# v1.net
KiCad netlist of a schematic drawn in EAGLE
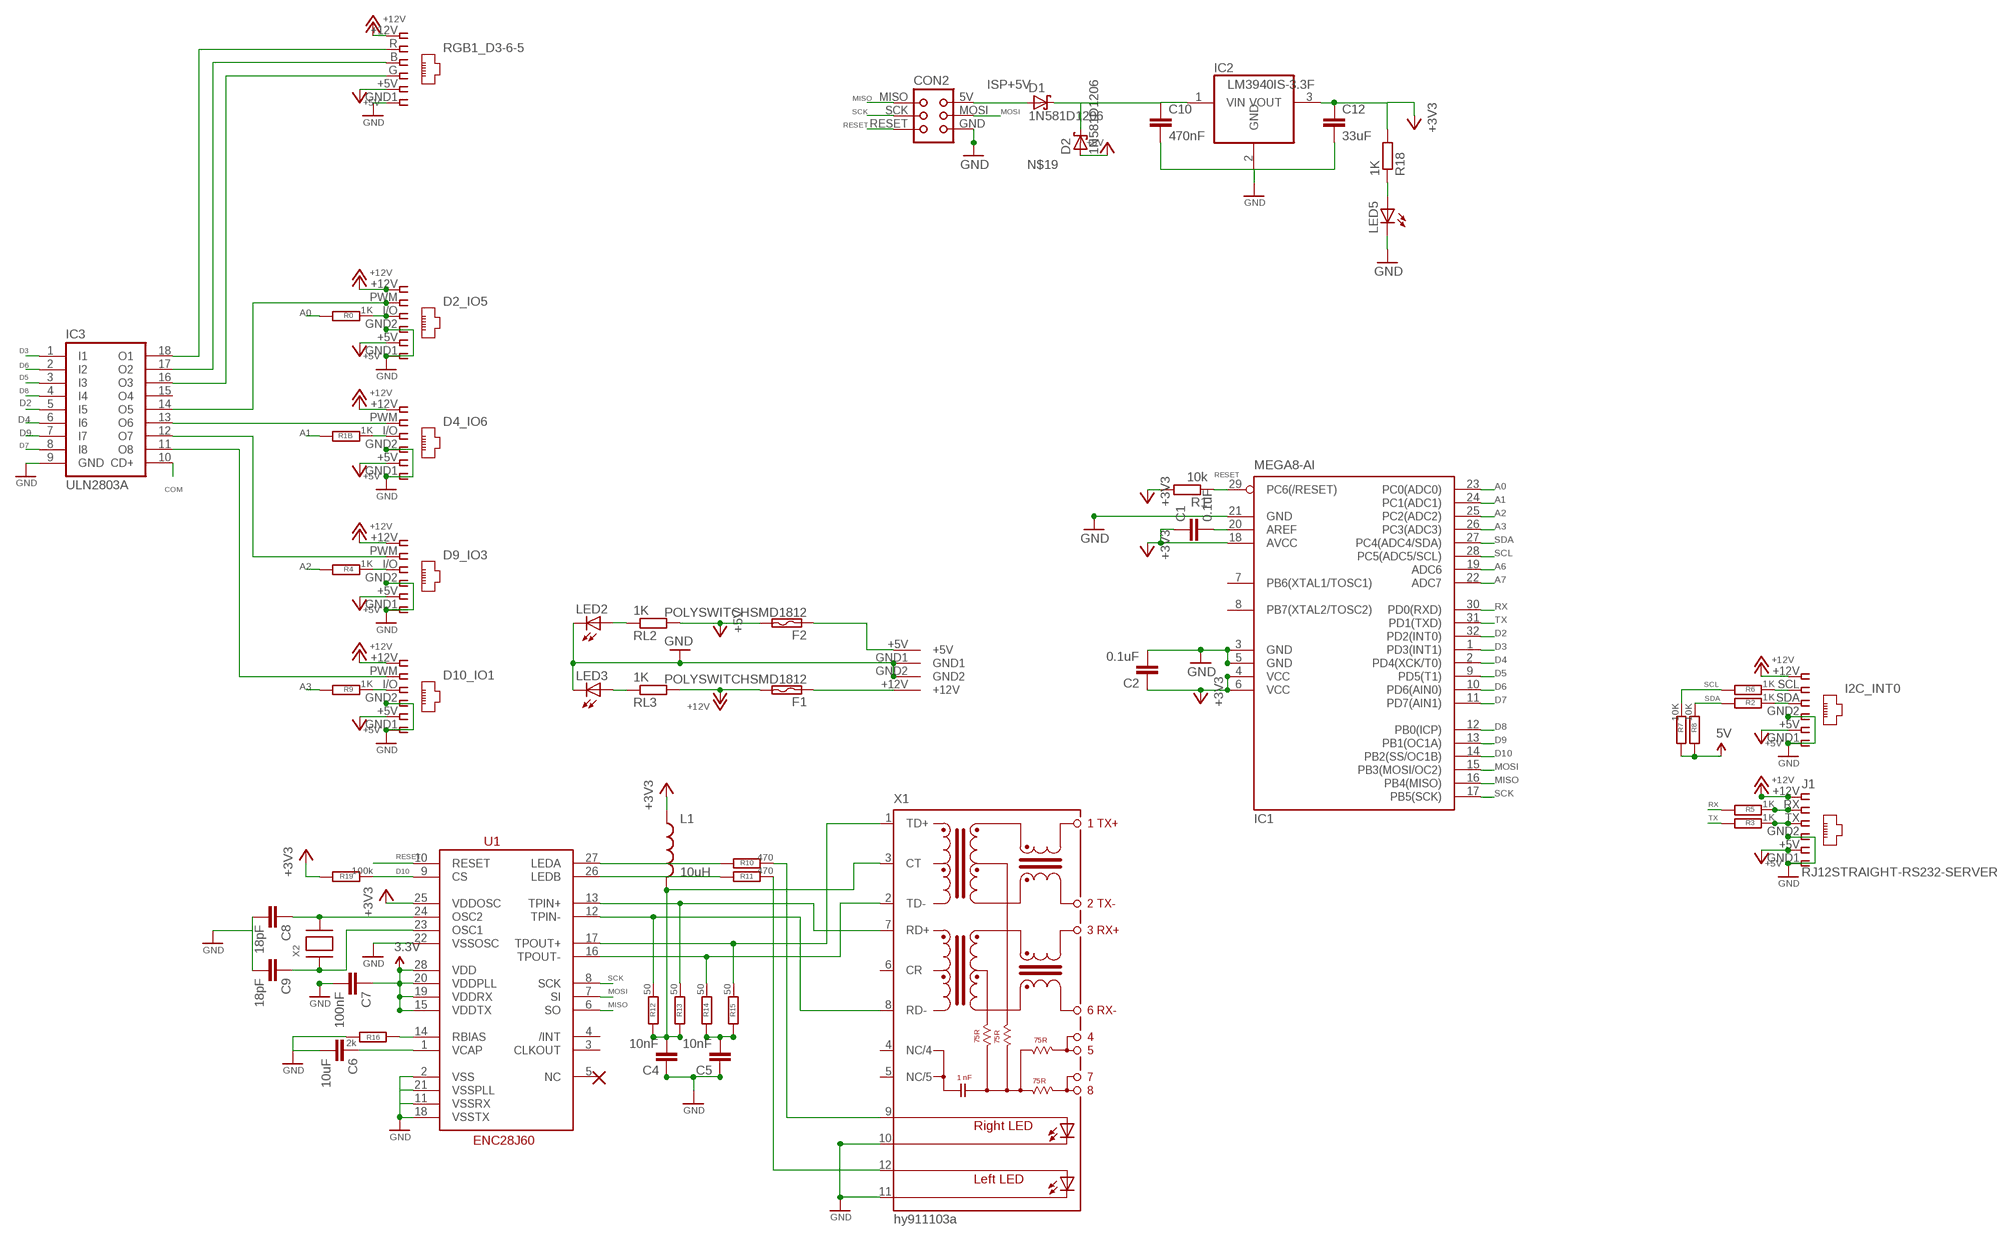
[diagram p0: schematic, sheet 1]

(export (version "E")
  (design (tool "Eeschema 10.0.6"))
  (components
    (comp (ref "C1")
      (value "0.1uF")
      (footprint "eagle-import:C1206")
      (libsource (lib "eagle-import") (part "resistor_C-EUC1206"))
    )
    (comp (ref "C2")
      (value "0.1uF")
      (footprint "eagle-import:C1206")
      (libsource (lib "eagle-import") (part "resistor_C-EUC1206"))
    )
    (comp (ref "C4")
      (value "10nF")
      (footprint "eagle-import:C1206")
      (libsource (lib "eagle-import") (part "resistor_C-EUC1206"))
    )
    (comp (ref "C5")
      (value "10nF")
      (footprint "eagle-import:C1206")
      (libsource (lib "eagle-import") (part "resistor_C-EUC1206"))
    )
    (comp (ref "C6")
      (value "10uF")
      (footprint "eagle-import:C1206")
      (libsource (lib "eagle-import") (part "resistor_C-EUC1206"))
    )
    (comp (ref "C7")
      (value "100nF")
      (footprint "eagle-import:C1206")
      (libsource (lib "eagle-import") (part "resistor_C-EUC1206"))
    )
    (comp (ref "C8")
      (value "18pF")
      (footprint "eagle-import:C1206")
      (libsource (lib "eagle-import") (part "resistor_C-EUC1206"))
    )
    (comp (ref "C9")
      (value "18pF")
      (footprint "eagle-import:C1206")
      (libsource (lib "eagle-import") (part "resistor_C-EUC1206"))
    )
    (comp (ref "C10")
      (value "470nF")
      (footprint "eagle-import:C1206")
      (libsource (lib "eagle-import") (part "C-EUC1206"))
    )
    (comp (ref "C12")
      (value "33uF")
      (footprint "eagle-import:1210")
      (libsource (lib "eagle-import") (part "CAP1210"))
    )
    (comp (ref "CON2")
      (value "TINYISPTAG")
      (footprint "eagle-import:TC2030-MCP")
      (libsource (lib "eagle-import") (part "TINYISPTAG"))
    )
    (comp (ref "D1")
      (value "1N581D1206")
      (footprint "eagle-import:LED-1206")
      (libsource (lib "eagle-import") (part "1N581D1206"))
    )
    (comp (ref "D2")
      (value "1N581D1206")
      (footprint "eagle-import:LED-1206")
      (libsource (lib "eagle-import") (part "1N581D1206"))
    )
    (comp (ref "D2_IO5")
      (value "IO5")
      (footprint "eagle-import:RJ12-STRAIGHT")
      (libsource (lib "eagle-import") (part "RJ12STRAIGHT"))
    )
    (comp (ref "D4_IO6")
      (value "IO6")
      (footprint "eagle-import:RJ12-STRAIGHT")
      (libsource (lib "eagle-import") (part "RJ12STRAIGHT"))
    )
    (comp (ref "D9_IO3")
      (value "IO3")
      (footprint "eagle-import:RJ12-STRAIGHT")
      (libsource (lib "eagle-import") (part "RJ12STRAIGHT"))
    )
    (comp (ref "D10_IO1")
      (value "IO1")
      (footprint "eagle-import:RJ12-STRAIGHT")
      (libsource (lib "eagle-import") (part "RJ12STRAIGHT"))
    )
    (comp (ref "F1")
      (value "POLYSWITCHSMD1812")
      (footprint "eagle-import:C1812")
      (libsource (lib "eagle-import") (part "POLYSWITCHSMD1812"))
    )
    (comp (ref "F2")
      (value "POLYSWITCHSMD1812")
      (footprint "eagle-import:C1812")
      (libsource (lib "eagle-import") (part "POLYSWITCHSMD1812"))
    )
    (comp (ref "I2C_INT0")
      (value "I2C")
      (footprint "eagle-import:RJ12-STRAIGHT-I2C")
      (libsource (lib "eagle-import") (part "RJ12STRAIGHT-I2C"))
    )
    (comp (ref "IC1")
      (value "MEGA8-AI")
      (footprint "eagle-import:TQFP32-08")
      (fields (field (name "MPN") "ATMEGA8-16AU"))
      (libsource (lib "eagle-import") (part "MEGA8-AI"))
    )
    (comp (ref "IC2")
      (value "LM3940IS-3.3F")
      (footprint "eagle-import:DD-3")
      (fields (field (name "MF") "TEXAS INSTRUMENTS") (field (name "MPN") "REG1117FAKTTT"))
      (libsource (lib "eagle-import") (part "LM3940IS-3.3F"))
    )
    (comp (ref "IC3")
      (value "ULN2803A")
      (footprint "eagle-import:SO18W")
      (libsource (lib "eagle-import") (part "ULN2803A"))
    )
    (comp (ref "J1")
      (value "RJ12STRAIGHT-RS232-SERVER")
      (footprint "eagle-import:RJ12-STRAIGHT-RS232")
      (libsource (lib "eagle-import") (part "RJ12STRAIGHT-RS232-SERVER"))
    )
    (comp (ref "L1")
      (value "10uH")
      (footprint "eagle-import:INDUCTOR-1206")
      (libsource (lib "eagle-import") (part "INDUCTORH1206"))
    )
    (comp (ref "LED2")
      (value "LED3MM")
      (footprint "eagle-import:LED3MM")
      (libsource (lib "eagle-import") (part "LED3MM"))
    )
    (comp (ref "LED3")
      (value "LED3MM")
      (footprint "eagle-import:LED3MM")
      (libsource (lib "eagle-import") (part "LED3MM"))
    )
    (comp (ref "LED5")
      (value "LED3MM")
      (footprint "eagle-import:LED3MM")
      (libsource (lib "eagle-import") (part "LED3MM"))
    )
    (comp (ref "R0")
      (value "1K")
      (footprint "eagle-import:M1206")
      (libsource (lib "eagle-import") (part "R-EU_M1206"))
    )
    (comp (ref "R1")
      (value "10k")
      (footprint "eagle-import:M1206")
      (libsource (lib "eagle-import") (part "R-EU_M1206"))
    )
    (comp (ref "R1B")
      (value "1K")
      (footprint "eagle-import:M1206")
      (libsource (lib "eagle-import") (part "R-EU_M1206"))
    )
    (comp (ref "R2")
      (value "1K")
      (footprint "eagle-import:M1206")
      (libsource (lib "eagle-import") (part "R-EU_M1206"))
    )
    (comp (ref "R3")
      (value "1K")
      (footprint "eagle-import:M1206")
      (libsource (lib "eagle-import") (part "R-EU_M1206"))
    )
    (comp (ref "R4")
      (value "1K")
      (footprint "eagle-import:M1206")
      (libsource (lib "eagle-import") (part "R-EU_M1206"))
    )
    (comp (ref "R5")
      (value "1K")
      (footprint "eagle-import:M1206")
      (libsource (lib "eagle-import") (part "R-EU_M1206"))
    )
    (comp (ref "R6")
      (value "1K")
      (footprint "eagle-import:M1206")
      (libsource (lib "eagle-import") (part "R-EU_M1206"))
    )
    (comp (ref "R7")
      (value "10K")
      (footprint "eagle-import:M1206")
      (libsource (lib "eagle-import") (part "R-EU_M1206"))
    )
    (comp (ref "R8")
      (value "10K")
      (footprint "eagle-import:M1206")
      (libsource (lib "eagle-import") (part "R-EU_M1206"))
    )
    (comp (ref "R9")
      (value "1K")
      (footprint "eagle-import:M1206")
      (libsource (lib "eagle-import") (part "R-EU_M1206"))
    )
    (comp (ref "R10")
      (value "470")
      (footprint "eagle-import:M1206")
      (libsource (lib "eagle-import") (part "R-EU_M1206"))
    )
    (comp (ref "R11")
      (value "470")
      (footprint "eagle-import:M1206")
      (libsource (lib "eagle-import") (part "R-EU_M1206"))
    )
    (comp (ref "R12")
      (value "50")
      (footprint "eagle-import:M1206")
      (libsource (lib "eagle-import") (part "R-EU_M1206"))
    )
    (comp (ref "R13")
      (value "50")
      (footprint "eagle-import:M1206")
      (libsource (lib "eagle-import") (part "R-EU_M1206"))
    )
    (comp (ref "R14")
      (value "50")
      (footprint "eagle-import:M1206")
      (libsource (lib "eagle-import") (part "R-EU_M1206"))
    )
    (comp (ref "R15")
      (value "50")
      (footprint "eagle-import:M1206")
      (libsource (lib "eagle-import") (part "R-EU_M1206"))
    )
    (comp (ref "R16")
      (value "2k")
      (footprint "eagle-import:M1206")
      (libsource (lib "eagle-import") (part "R-EU_M1206"))
    )
    (comp (ref "R18")
      (value "1K")
      (footprint "eagle-import:M1206")
      (libsource (lib "eagle-import") (part "R-EU_M1206"))
    )
    (comp (ref "R19")
      (value "100k")
      (footprint "eagle-import:M1206")
      (libsource (lib "eagle-import") (part "R-EU_M1206"))
    )
    (comp (ref "RGB1_D3-6-5")
      (value "RGB1")
      (footprint "eagle-import:RJ12-STRAIGHT-RGB")
      (libsource (lib "eagle-import") (part "RJ12STRAIGHT-RGB"))
    )
    (comp (ref "RL2")
      (value "1K")
      (footprint "eagle-import:M1206")
      (libsource (lib "eagle-import") (part "R-EU_M1206"))
    )
    (comp (ref "RL3")
      (value "1K")
      (footprint "eagle-import:M1206")
      (libsource (lib "eagle-import") (part "R-EU_M1206"))
    )
    (comp (ref "U$2")
      (value "KPJX-4S-S")
      (footprint "eagle-import:KPJX-4S-S")
      (libsource (lib "eagle-import") (part "KPJX-4S-S"))
    )
    (comp (ref "U1")
      (value "ENC28J60SO")
      (footprint "eagle-import:SO28W")
      (libsource (lib "eagle-import") (part "ENC28J60SO"))
    )
    (comp (ref "X1")
      (value "hy911103a")
      (footprint "eagle-import:J1")
      (libsource (lib "eagle-import") (part "J1011F01P"))
    )
    (comp (ref "X2")
      (value "XTALNX5032")
      (footprint "eagle-import:NX5032")
      (libsource (lib "eagle-import") (part "XTALNX5032"))
    )
  )
  (nets
    (net (code "1") (name "+3V3") (class "Default")
      (node (ref "C1") (pin "1") (pinfunction "1_1") (pintype "passive"))
      (node (ref "C12") (pin "1") (pinfunction "1_1") (pintype "passive"))
      (node (ref "C2") (pin "1") (pinfunction "1_1") (pintype "passive"))
      (node (ref "IC1") (pin "18") (pinfunction "AVCC_18") (pintype "power_in"))
      (node (ref "IC1") (pin "4") (pinfunction "VCC_4") (pintype "power_in"))
      (node (ref "IC1") (pin "6") (pinfunction "VCC_6") (pintype "power_in"))
      (node (ref "IC2") (pin "3") (pinfunction "VOUT_3") (pintype "output"))
      (node (ref "L1") (pin "P$1") (pinfunction "1_P$1") (pintype "passive"))
      (node (ref "R1") (pin "2") (pinfunction "2_2") (pintype "passive"))
      (node (ref "R18") (pin "2") (pinfunction "2_2") (pintype "passive"))
      (node (ref "R19") (pin "2") (pinfunction "2_2") (pintype "passive"))
      (node (ref "U1") (pin "25") (pinfunction "VDDOSC_25") (pintype "bidirectional"))
    )
    (net (code "2") (name "+5V") (class "Default")
      (node (ref "D10_IO1") (pin "+5V") (pinfunction "5_+5V") (pintype "power_in"))
      (node (ref "D2") (pin "A") (pinfunction "A_A") (pintype "passive"))
      (node (ref "D2_IO5") (pin "+5V") (pinfunction "5_+5V") (pintype "power_in"))
      (node (ref "D4_IO6") (pin "+5V") (pinfunction "5_+5V") (pintype "power_in"))
      (node (ref "D9_IO3") (pin "+5V") (pinfunction "5_+5V") (pintype "power_in"))
      (node (ref "F2") (pin "2") (pinfunction "2_2") (pintype "passive"))
      (node (ref "I2C_INT0") (pin "+5V") (pinfunction "5_+5V") (pintype "power_in"))
      (node (ref "J1") (pin "+5V") (pinfunction "5_+5V") (pintype "power_in"))
      (node (ref "RGB1_D3-6-5") (pin "+5V") (pinfunction "5_+5V") (pintype "power_in"))
      (node (ref "RL2") (pin "2") (pinfunction "2_2") (pintype "passive"))
    )
    (net (code "3") (name "+12V") (class "Default")
      (node (ref "D10_IO1") (pin "+12V") (pinfunction "1_+12V") (pintype "power_in"))
      (node (ref "D2_IO5") (pin "+12V") (pinfunction "1_+12V") (pintype "power_in"))
      (node (ref "D4_IO6") (pin "+12V") (pinfunction "1_+12V") (pintype "power_in"))
      (node (ref "D9_IO3") (pin "+12V") (pinfunction "1_+12V") (pintype "power_in"))
      (node (ref "F1") (pin "2") (pinfunction "2_2") (pintype "passive"))
      (node (ref "I2C_INT0") (pin "+12V") (pinfunction "1_+12V") (pintype "power_in"))
      (node (ref "J1") (pin "+12V") (pinfunction "1_+12V") (pintype "power_in"))
      (node (ref "RGB1_D3-6-5") (pin "+12V") (pinfunction "1_+12V") (pintype "power_in"))
      (node (ref "RL3") (pin "2") (pinfunction "2_2") (pintype "passive"))
    )
    (net (code "4") (name "/A0") (class "Default")
      (node (ref "IC1") (pin "23") (pinfunction "PC0(ADC0)_23") (pintype "bidirectional"))
      (node (ref "R0") (pin "2") (pinfunction "2_2") (pintype "passive"))
    )
    (net (code "5") (name "/A1") (class "Default")
      (node (ref "IC1") (pin "24") (pinfunction "PC1(ADC1)_24") (pintype "bidirectional"))
      (node (ref "R1B") (pin "2") (pinfunction "2_2") (pintype "passive"))
    )
    (net (code "6") (name "/A2") (class "Default")
      (node (ref "IC1") (pin "25") (pinfunction "PC2(ADC2)_25") (pintype "bidirectional"))
      (node (ref "R4") (pin "2") (pinfunction "2_2") (pintype "passive"))
    )
    (net (code "7") (name "/A3") (class "Default")
      (node (ref "IC1") (pin "26") (pinfunction "PC3(ADC3)_26") (pintype "bidirectional"))
      (node (ref "R9") (pin "2") (pinfunction "2_2") (pintype "passive"))
    )
    (net (code "8") (name "/A6") (class "Default")
      (node (ref "IC1") (pin "19") (pinfunction "ADC6_19") (pintype "bidirectional"))
    )
    (net (code "9") (name "/A7") (class "Default")
      (node (ref "IC1") (pin "22") (pinfunction "ADC7_22") (pintype "bidirectional"))
    )
    (net (code "10") (name "/COM") (class "Default")
      (node (ref "IC3") (pin "10") (pinfunction "CD+_10") (pintype "passive"))
    )
    (net (code "11") (name "/D2") (class "Default")
      (node (ref "IC1") (pin "32") (pinfunction "PD2(INT0)_32") (pintype "bidirectional"))
      (node (ref "IC3") (pin "5") (pinfunction "I5_5") (pintype "input"))
    )
    (net (code "12") (name "/D3") (class "Default")
      (node (ref "IC1") (pin "1") (pinfunction "PD3(INT1)_1") (pintype "bidirectional"))
      (node (ref "IC3") (pin "1") (pinfunction "I1_1") (pintype "input"))
    )
    (net (code "13") (name "/D4") (class "Default")
      (node (ref "IC1") (pin "2") (pinfunction "PD4(XCK/T0)_2") (pintype "bidirectional"))
      (node (ref "IC3") (pin "6") (pinfunction "I6_6") (pintype "input"))
    )
    (net (code "14") (name "/D5") (class "Default")
      (node (ref "IC1") (pin "9") (pinfunction "PD5(T1)_9") (pintype "bidirectional"))
      (node (ref "IC3") (pin "3") (pinfunction "I3_3") (pintype "input"))
    )
    (net (code "15") (name "/D6") (class "Default")
      (node (ref "IC1") (pin "10") (pinfunction "PD6(AIN0)_10") (pintype "bidirectional"))
      (node (ref "IC3") (pin "2") (pinfunction "I2_2") (pintype "input"))
    )
    (net (code "16") (name "/D7") (class "Default")
      (node (ref "IC1") (pin "11") (pinfunction "PD7(AIN1)_11") (pintype "bidirectional"))
      (node (ref "IC3") (pin "8") (pinfunction "I8_8") (pintype "input"))
    )
    (net (code "17") (name "/D8") (class "Default")
      (node (ref "IC1") (pin "12") (pinfunction "PB0(ICP)_12") (pintype "bidirectional"))
      (node (ref "IC3") (pin "4") (pinfunction "I4_4") (pintype "input"))
    )
    (net (code "18") (name "/D9") (class "Default")
      (node (ref "IC1") (pin "13") (pinfunction "PB1(OC1A)_13") (pintype "bidirectional"))
      (node (ref "IC3") (pin "7") (pinfunction "I7_7") (pintype "input"))
    )
    (net (code "19") (name "/D10") (class "Default")
      (node (ref "IC1") (pin "14") (pinfunction "PB2(SS/OC1B)_14") (pintype "bidirectional"))
      (node (ref "R19") (pin "1") (pinfunction "1_1") (pintype "passive"))
      (node (ref "U1") (pin "9") (pinfunction "CS_9") (pintype "bidirectional"))
    )
    (net (code "20") (name "/ISP+5V") (class "Default")
      (node (ref "CON2") (pin "5V") (pinfunction "VCC_5V") (pintype "passive"))
      (node (ref "D1") (pin "A") (pinfunction "A_A") (pintype "passive"))
    )
    (net (code "21") (name "/MISO") (class "Default")
      (node (ref "CON2") (pin "MISO") (pinfunction "MISO_MISO") (pintype "passive"))
      (node (ref "IC1") (pin "16") (pinfunction "PB4(MISO)_16") (pintype "bidirectional"))
      (node (ref "U1") (pin "6") (pinfunction "SO_6") (pintype "bidirectional"))
    )
    (net (code "22") (name "/MOSI") (class "Default")
      (node (ref "CON2") (pin "MOSI") (pinfunction "MOSI_MOSI") (pintype "passive"))
      (node (ref "IC1") (pin "15") (pinfunction "PB3(MOSI/OC2)_15") (pintype "bidirectional"))
      (node (ref "U1") (pin "7") (pinfunction "SI_7") (pintype "bidirectional"))
    )
    (net (code "23") (name "/N$19") (class "Default")
      (node (ref "C10") (pin "1") (pinfunction "1_1") (pintype "passive"))
      (node (ref "D1") (pin "C") (pinfunction "C_C") (pintype "passive"))
      (node (ref "D2") (pin "C") (pinfunction "C_C") (pintype "passive"))
      (node (ref "IC2") (pin "1") (pinfunction "VIN_1") (pintype "input"))
    )
    (net (code "24") (name "/RESET") (class "Default")
      (node (ref "CON2") (pin "RESET") (pinfunction "RESET_RESET") (pintype "passive"))
      (node (ref "IC1") (pin "29") (pinfunction "PC6(/RESET)_29") (pintype "bidirectional"))
      (node (ref "R1") (pin "1") (pinfunction "1_1") (pintype "passive"))
      (node (ref "U1") (pin "10") (pinfunction "RESET_10") (pintype "bidirectional"))
    )
    (net (code "25") (name "/RX") (class "Default")
      (node (ref "IC1") (pin "30") (pinfunction "PD0(RXD)_30") (pintype "bidirectional"))
      (node (ref "R5") (pin "2") (pinfunction "2_2") (pintype "passive"))
    )
    (net (code "26") (name "/SCK") (class "Default")
      (node (ref "CON2") (pin "SCK") (pinfunction "SCK_SCK") (pintype "passive"))
      (node (ref "IC1") (pin "17") (pinfunction "PB5(SCK)_17") (pintype "bidirectional"))
      (node (ref "U1") (pin "8") (pinfunction "SCK_8") (pintype "bidirectional"))
    )
    (net (code "27") (name "/SCL") (class "Default")
      (node (ref "IC1") (pin "28") (pinfunction "PC5(ADC5/SCL)_28") (pintype "bidirectional"))
      (node (ref "R6") (pin "2") (pinfunction "2_2") (pintype "passive"))
      (node (ref "R7") (pin "1") (pinfunction "1_1") (pintype "passive"))
    )
    (net (code "28") (name "/SDA") (class "Default")
      (node (ref "IC1") (pin "27") (pinfunction "PC4(ADC4/SDA)_27") (pintype "bidirectional"))
      (node (ref "R2") (pin "2") (pinfunction "2_2") (pintype "passive"))
      (node (ref "R8") (pin "1") (pinfunction "1_1") (pintype "passive"))
    )
    (net (code "29") (name "/TX") (class "Default")
      (node (ref "IC1") (pin "31") (pinfunction "PD1(TXD)_31") (pintype "bidirectional"))
      (node (ref "R3") (pin "2") (pinfunction "2_2") (pintype "passive"))
    )
    (net (code "30") (name "3.3V") (class "Default")
      (node (ref "C7") (pin "1") (pinfunction "1_1") (pintype "passive"))
      (node (ref "U1") (pin "15") (pinfunction "VDDTX_15") (pintype "bidirectional"))
      (node (ref "U1") (pin "19") (pinfunction "VDDRX_19") (pintype "bidirectional"))
      (node (ref "U1") (pin "20") (pinfunction "VDDPLL_20") (pintype "bidirectional"))
      (node (ref "U1") (pin "28") (pinfunction "VDD_28") (pintype "bidirectional"))
    )
    (net (code "31") (name "5V") (class "Default")
      (node (ref "R7") (pin "2") (pinfunction "2_2") (pintype "passive"))
      (node (ref "R8") (pin "2") (pinfunction "2_2") (pintype "passive"))
    )
    (net (code "32") (name "GND") (class "Default")
      (node (ref "C10") (pin "2") (pinfunction "2_2") (pintype "passive"))
      (node (ref "C12") (pin "2") (pinfunction "2_2") (pintype "passive"))
      (node (ref "C2") (pin "2") (pinfunction "2_2") (pintype "passive"))
      (node (ref "C4") (pin "1") (pinfunction "1_1") (pintype "passive"))
      (node (ref "C5") (pin "1") (pinfunction "1_1") (pintype "passive"))
      (node (ref "C6") (pin "2") (pinfunction "2_2") (pintype "passive"))
      (node (ref "C7") (pin "2") (pinfunction "2_2") (pintype "passive"))
      (node (ref "C8") (pin "2") (pinfunction "2_2") (pintype "passive"))
      (node (ref "C9") (pin "2") (pinfunction "2_2") (pintype "passive"))
      (node (ref "CON2") (pin "GND") (pinfunction "GND_GND") (pintype "passive"))
      (node (ref "D10_IO1") (pin "GND1") (pinfunction "6_GND1") (pintype "power_in"))
      (node (ref "D10_IO1") (pin "GND2") (pinfunction "4_GND2") (pintype "power_in"))
      (node (ref "D2_IO5") (pin "GND1") (pinfunction "6_GND1") (pintype "power_in"))
      (node (ref "D2_IO5") (pin "GND2") (pinfunction "4_GND2") (pintype "power_in"))
      (node (ref "D4_IO6") (pin "GND1") (pinfunction "6_GND1") (pintype "power_in"))
      (node (ref "D4_IO6") (pin "GND2") (pinfunction "4_GND2") (pintype "power_in"))
      (node (ref "D9_IO3") (pin "GND1") (pinfunction "6_GND1") (pintype "power_in"))
      (node (ref "D9_IO3") (pin "GND2") (pinfunction "4_GND2") (pintype "power_in"))
      (node (ref "I2C_INT0") (pin "GND1") (pinfunction "6_GND1") (pintype "power_in"))
      (node (ref "I2C_INT0") (pin "GND2") (pinfunction "4_GND2") (pintype "power_in"))
      (node (ref "IC1") (pin "21") (pinfunction "GND_21") (pintype "power_in"))
      (node (ref "IC1") (pin "3") (pinfunction "GND_3") (pintype "power_in"))
      (node (ref "IC1") (pin "5") (pinfunction "GND_5") (pintype "power_in"))
      (node (ref "IC2") (pin "2") (pinfunction "GND_2") (pintype "power_in"))
      (node (ref "IC3") (pin "9") (pinfunction "GND_9") (pintype "power_in"))
      (node (ref "J1") (pin "GND1") (pinfunction "6_GND1") (pintype "power_in"))
      (node (ref "J1") (pin "GND2") (pinfunction "4_GND2") (pintype "power_in"))
      (node (ref "LED2") (pin "K") (pinfunction "C_K") (pintype "passive"))
      (node (ref "LED3") (pin "K") (pinfunction "C_K") (pintype "passive"))
      (node (ref "LED5") (pin "K") (pinfunction "C_K") (pintype "passive"))
      (node (ref "R16") (pin "1") (pinfunction "1_1") (pintype "passive"))
      (node (ref "RGB1_D3-6-5") (pin "GND1") (pinfunction "6_GND1") (pintype "power_in"))
      (node (ref "U$2") (pin "GND1") (pinfunction "GND1_GND1") (pintype "input"))
      (node (ref "U$2") (pin "GND2") (pinfunction "GND2_GND2") (pintype "input"))
      (node (ref "U1") (pin "11") (pinfunction "VSSRX_11") (pintype "bidirectional"))
      (node (ref "U1") (pin "18") (pinfunction "VSSTX_18") (pintype "bidirectional"))
      (node (ref "U1") (pin "2") (pinfunction "VSS_2") (pintype "bidirectional"))
      (node (ref "U1") (pin "21") (pinfunction "VSSPLL_21") (pintype "bidirectional"))
      (node (ref "U1") (pin "22") (pinfunction "VSSOSC_22") (pintype "bidirectional"))
      (node (ref "X1") (pin "10") (pinfunction "C-R_10") (pintype "passive"))
      (node (ref "X1") (pin "11") (pinfunction "C-L_11") (pintype "passive"))
    )
    (net (code "33") (name "Net-(C5-Pad2)") (class "Default")
      (node (ref "C5") (pin "2") (pinfunction "2_2") (pintype "passive"))
      (node (ref "R14") (pin "2") (pinfunction "2_2") (pintype "passive"))
      (node (ref "R15") (pin "2") (pinfunction "2_2") (pintype "passive"))
    )
    (net (code "34") (name "Net-(D2_IO5-2)") (class "Default")
      (node (ref "D2_IO5") (pin "PWM") (pinfunction "2_PWM") (pintype "bidirectional"))
      (node (ref "IC3") (pin "14") (pinfunction "O5_14") (pintype "open_collector"))
    )
    (net (code "35") (name "Net-(D2_IO5-3)") (class "Default")
      (node (ref "D2_IO5") (pin "I/O") (pinfunction "3_I/O") (pintype "bidirectional"))
      (node (ref "R0") (pin "1") (pinfunction "1_1") (pintype "passive"))
    )
    (net (code "36") (name "Net-(D4_IO6-2)") (class "Default")
      (node (ref "D4_IO6") (pin "PWM") (pinfunction "2_PWM") (pintype "bidirectional"))
      (node (ref "IC3") (pin "13") (pinfunction "O6_13") (pintype "open_collector"))
    )
    (net (code "37") (name "Net-(D4_IO6-3)") (class "Default")
      (node (ref "D4_IO6") (pin "I/O") (pinfunction "3_I/O") (pintype "bidirectional"))
      (node (ref "R1B") (pin "1") (pinfunction "1_1") (pintype "passive"))
    )
    (net (code "38") (name "Net-(D9_IO3-2)") (class "Default")
      (node (ref "D9_IO3") (pin "PWM") (pinfunction "2_PWM") (pintype "bidirectional"))
      (node (ref "IC3") (pin "12") (pinfunction "O7_12") (pintype "open_collector"))
    )
    (net (code "39") (name "Net-(D9_IO3-3)") (class "Default")
      (node (ref "D9_IO3") (pin "I/O") (pinfunction "3_I/O") (pintype "bidirectional"))
      (node (ref "R4") (pin "1") (pinfunction "1_1") (pintype "passive"))
    )
    (net (code "40") (name "Net-(D10_IO1-2)") (class "Default")
      (node (ref "D10_IO1") (pin "PWM") (pinfunction "2_PWM") (pintype "bidirectional"))
      (node (ref "IC3") (pin "11") (pinfunction "O8_11") (pintype "open_collector"))
    )
    (net (code "41") (name "Net-(D10_IO1-3)") (class "Default")
      (node (ref "D10_IO1") (pin "I/O") (pinfunction "3_I/O") (pintype "bidirectional"))
      (node (ref "R9") (pin "1") (pinfunction "1_1") (pintype "passive"))
    )
    (net (code "42") (name "Net-(F1-Pad1)") (class "Default")
      (node (ref "F1") (pin "1") (pinfunction "1_1") (pintype "passive"))
      (node (ref "U$2") (pin "+12V") (pinfunction "+12V_+12V") (pintype "power_in"))
    )
    (net (code "43") (name "Net-(F2-Pad1)") (class "Default")
      (node (ref "F2") (pin "1") (pinfunction "1_1") (pintype "passive"))
      (node (ref "U$2") (pin "+5V") (pinfunction "+5V_+5V") (pintype "power_in"))
    )
    (net (code "44") (name "Net-(I2C_INT0-2)") (class "Default")
      (node (ref "I2C_INT0") (pin "SCL") (pinfunction "2_SCL") (pintype "bidirectional"))
      (node (ref "R6") (pin "1") (pinfunction "1_1") (pintype "passive"))
    )
    (net (code "45") (name "Net-(I2C_INT0-3)") (class "Default")
      (node (ref "I2C_INT0") (pin "SDA") (pinfunction "3_SDA") (pintype "bidirectional"))
      (node (ref "R2") (pin "1") (pinfunction "1_1") (pintype "passive"))
    )
    (net (code "46") (name "Net-(IC1-AREF)") (class "Default")
      (node (ref "C1") (pin "2") (pinfunction "2_2") (pintype "passive"))
      (node (ref "IC1") (pin "20") (pinfunction "AREF_20") (pintype "passive"))
    )
    (net (code "47") (name "Net-(IC3-O1)") (class "Default")
      (node (ref "IC3") (pin "18") (pinfunction "O1_18") (pintype "open_collector"))
      (node (ref "RGB1_D3-6-5") (pin "R") (pinfunction "2_R") (pintype "bidirectional"))
    )
    (net (code "48") (name "Net-(IC3-O2)") (class "Default")
      (node (ref "IC3") (pin "17") (pinfunction "O2_17") (pintype "open_collector"))
      (node (ref "RGB1_D3-6-5") (pin "B") (pinfunction "3_B") (pintype "bidirectional"))
    )
    (net (code "49") (name "Net-(IC3-O3)") (class "Default")
      (node (ref "IC3") (pin "16") (pinfunction "O3_16") (pintype "open_collector"))
      (node (ref "RGB1_D3-6-5") (pin "G") (pinfunction "4_G") (pintype "power_in"))
    )
    (net (code "50") (name "Net-(J1-2)") (class "Default")
      (node (ref "J1") (pin "RX") (pinfunction "2_RX") (pintype "bidirectional"))
      (node (ref "R5") (pin "1") (pinfunction "1_1") (pintype "passive"))
    )
    (net (code "51") (name "Net-(J1-3)") (class "Default")
      (node (ref "J1") (pin "TX") (pinfunction "3_TX") (pintype "bidirectional"))
      (node (ref "R3") (pin "1") (pinfunction "1_1") (pintype "passive"))
    )
    (net (code "52") (name "Net-(L1-2)") (class "Default")
      (node (ref "C4") (pin "2") (pinfunction "2_2") (pintype "passive"))
      (node (ref "L1") (pin "P$2") (pinfunction "2_P$2") (pintype "passive"))
      (node (ref "R12") (pin "2") (pinfunction "2_2") (pintype "passive"))
      (node (ref "R13") (pin "2") (pinfunction "2_2") (pintype "passive"))
      (node (ref "X1") (pin "3") (pinfunction "CT_3") (pintype "input"))
    )
    (net (code "53") (name "Net-(LED2-PadA)") (class "Default")
      (node (ref "LED2") (pin "A") (pinfunction "A_A") (pintype "passive"))
      (node (ref "RL2") (pin "1") (pinfunction "1_1") (pintype "passive"))
    )
    (net (code "54") (name "Net-(LED3-PadA)") (class "Default")
      (node (ref "LED3") (pin "A") (pinfunction "A_A") (pintype "passive"))
      (node (ref "RL3") (pin "1") (pinfunction "1_1") (pintype "passive"))
    )
    (net (code "55") (name "Net-(LED5-PadA)") (class "Default")
      (node (ref "LED5") (pin "A") (pinfunction "A_A") (pintype "passive"))
      (node (ref "R18") (pin "1") (pinfunction "1_1") (pintype "passive"))
    )
    (net (code "56") (name "Net-(U1-LEDA)") (class "Default")
      (node (ref "R10") (pin "2") (pinfunction "2_2") (pintype "passive"))
      (node (ref "U1") (pin "27") (pinfunction "LEDA_27") (pintype "bidirectional"))
    )
    (net (code "57") (name "Net-(U1-LEDB)") (class "Default")
      (node (ref "R11") (pin "2") (pinfunction "2_2") (pintype "passive"))
      (node (ref "U1") (pin "26") (pinfunction "LEDB_26") (pintype "bidirectional"))
    )
    (net (code "58") (name "Net-(U1-OSC1)") (class "Default")
      (node (ref "C9") (pin "1") (pinfunction "1_1") (pintype "passive"))
      (node (ref "U1") (pin "23") (pinfunction "OSC1_23") (pintype "bidirectional"))
      (node (ref "X2") (pin "P$1") (pinfunction "P$1_P$1") (pintype "bidirectional"))
    )
    (net (code "59") (name "Net-(U1-OSC2)") (class "Default")
      (node (ref "C8") (pin "1") (pinfunction "1_1") (pintype "passive"))
      (node (ref "U1") (pin "24") (pinfunction "OSC2_24") (pintype "bidirectional"))
      (node (ref "X2") (pin "P$2") (pinfunction "P$2_P$2") (pintype "bidirectional"))
    )
    (net (code "60") (name "Net-(U1-RBIAS)") (class "Default")
      (node (ref "R16") (pin "2") (pinfunction "2_2") (pintype "passive"))
      (node (ref "U1") (pin "14") (pinfunction "RBIAS_14") (pintype "bidirectional"))
    )
    (net (code "61") (name "Net-(U1-TPIN+)") (class "Default")
      (node (ref "R13") (pin "1") (pinfunction "1_1") (pintype "passive"))
      (node (ref "U1") (pin "13") (pinfunction "TPIN+_13") (pintype "bidirectional"))
      (node (ref "X1") (pin "7") (pinfunction "RD+_7") (pintype "input"))
    )
    (net (code "62") (name "Net-(U1-TPIN-)") (class "Default")
      (node (ref "R12") (pin "1") (pinfunction "1_1") (pintype "passive"))
      (node (ref "U1") (pin "12") (pinfunction "TPIN-_12") (pintype "bidirectional"))
      (node (ref "X1") (pin "8") (pinfunction "RD-_8") (pintype "input"))
    )
    (net (code "63") (name "Net-(U1-TPOUT+)") (class "Default")
      (node (ref "R15") (pin "1") (pinfunction "1_1") (pintype "passive"))
      (node (ref "U1") (pin "17") (pinfunction "TPOUT+_17") (pintype "bidirectional"))
      (node (ref "X1") (pin "1") (pinfunction "TD+_1") (pintype "input"))
    )
    (net (code "64") (name "Net-(U1-TPOUT-)") (class "Default")
      (node (ref "R14") (pin "1") (pinfunction "1_1") (pintype "passive"))
      (node (ref "U1") (pin "16") (pinfunction "TPOUT-_16") (pintype "bidirectional"))
      (node (ref "X1") (pin "2") (pinfunction "TD-_2") (pintype "input"))
    )
    (net (code "65") (name "Net-(U1-VCAP)") (class "Default")
      (node (ref "C6") (pin "1") (pinfunction "1_1") (pintype "passive"))
      (node (ref "U1") (pin "1") (pinfunction "VCAP_1") (pintype "bidirectional"))
    )
    (net (code "66") (name "Net-(X1-A-R)") (class "Default")
      (node (ref "R10") (pin "1") (pinfunction "1_1") (pintype "passive"))
      (node (ref "X1") (pin "9") (pinfunction "A-R_9") (pintype "passive"))
    )
    (net (code "67") (name "Net-(X1-AL)") (class "Default")
      (node (ref "R11") (pin "1") (pinfunction "1_1") (pintype "passive"))
      (node (ref "X1") (pin "12") (pinfunction "AL_12") (pintype "passive"))
    )
    (net (code "68") (name "unconnected-(IC1-PB6(XTAL1{slash}TOSC1)-Pad7)") (class "Default")
      (node (ref "IC1") (pin "7") (pinfunction "PB6(XTAL1/TOSC1)_7") (pintype "bidirectional"))
    )
    (net (code "69") (name "unconnected-(IC1-PB7(XTAL2{slash}TOSC2)-Pad8)") (class "Default")
      (node (ref "IC1") (pin "8") (pinfunction "PB7(XTAL2/TOSC2)_8") (pintype "bidirectional"))
    )
    (net (code "70") (name "unconnected-(IC3-O4-Pad15)") (class "Default")
      (node (ref "IC3") (pin "15") (pinfunction "O4_15") (pintype "open_collector"))
    )
    (net (code "71") (name "unconnected-(U1-CLKOUT-Pad3)") (class "Default")
      (node (ref "U1") (pin "3") (pinfunction "CLKOUT_3") (pintype "bidirectional"))
    )
    (net (code "72") (name "unconnected-(U1-NC-Pad5)") (class "Default")
      (node (ref "U1") (pin "5") (pinfunction "NC_5") (pintype "bidirectional"))
    )
    (net (code "73") (name "unconnected-(U1-{slash}INT-Pad4)") (class "Default")
      (node (ref "U1") (pin "4") (pinfunction "/INT_4") (pintype "bidirectional"))
    )
    (net (code "74") (name "unconnected-(X1-CR-Pad6)") (class "Default")
      (node (ref "X1") (pin "6") (pinfunction "CR_6") (pintype "input"))
    )
    (net (code "75") (name "unconnected-(X1-NC{slash}4-Pad4)") (class "Default")
      (node (ref "X1") (pin "4") (pinfunction "NC/4_4") (pintype "input"))
    )
    (net (code "76") (name "unconnected-(X1-NC{slash}5-Pad5)") (class "Default")
      (node (ref "X1") (pin "5") (pinfunction "NC/5_5") (pintype "input"))
    )
  )
)
